# Sheet1.net
KiCad netlist of a schematic drawn in Altium Designer
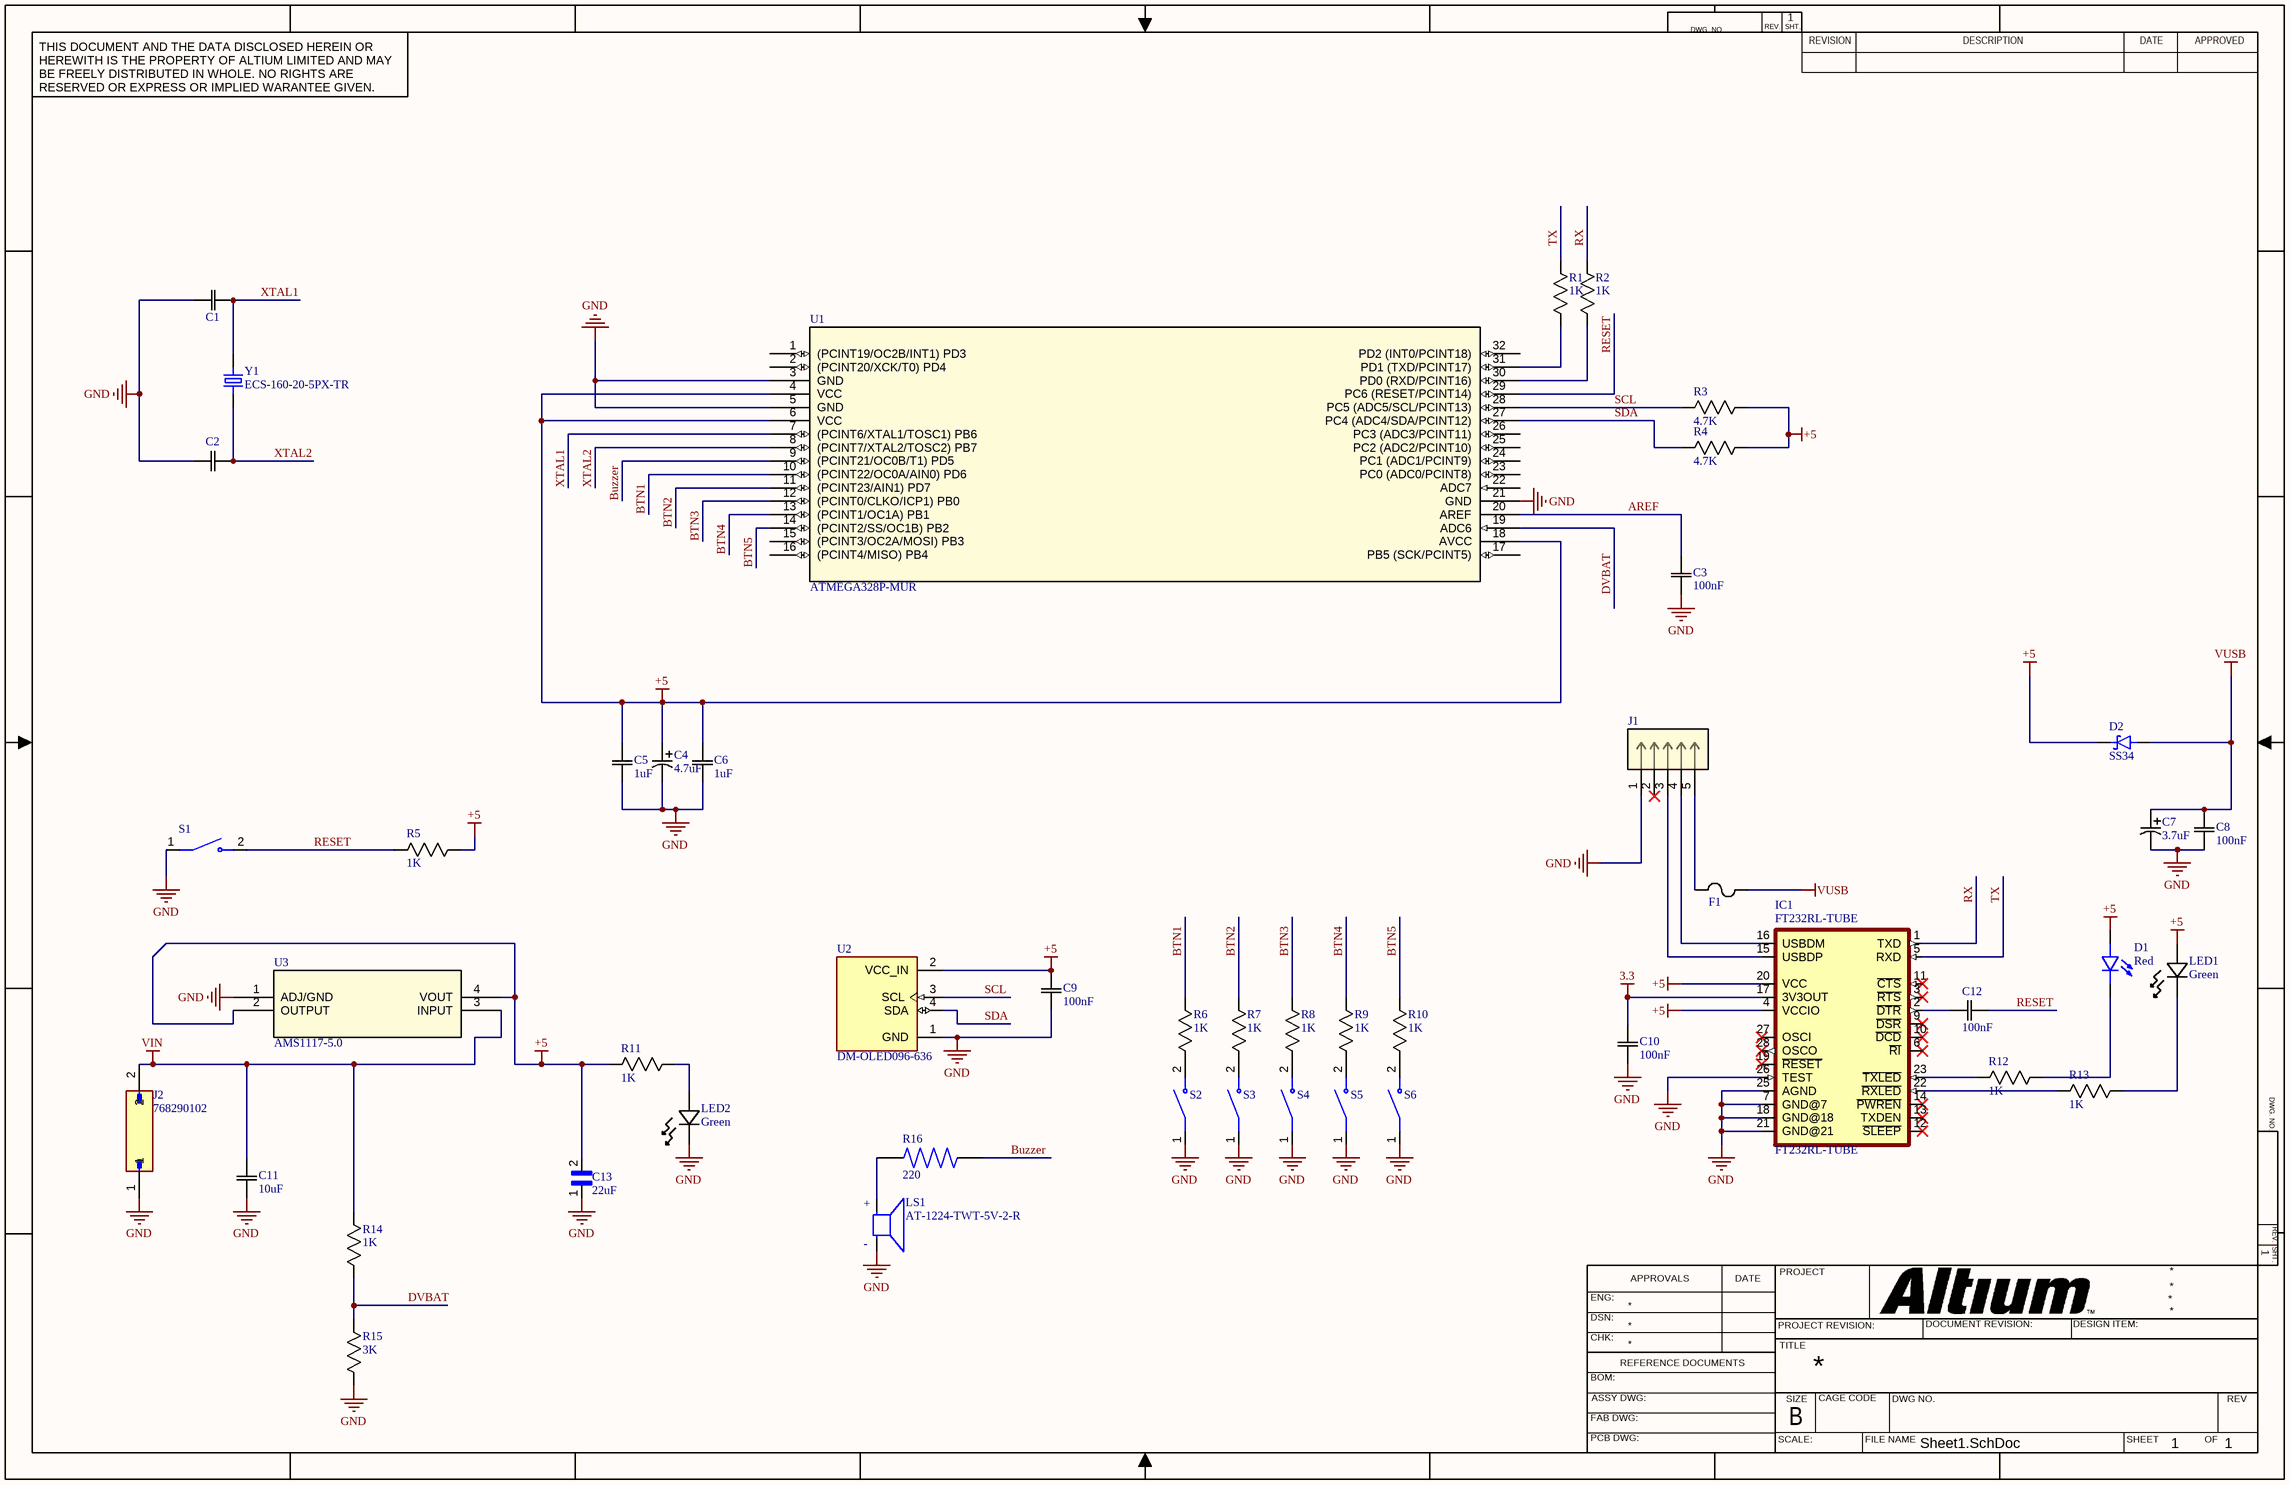
[diagram p0: Sheet1.SchDoc]

(export (version "E")
  (design (tool "Eeschema 10.0.6"))
  (components
    (comp (ref "C1")
      (value "CAP_18pfar_805pkg")
      (footprint "CAP_CC0805_YAG")
      (description "No Description Available")
      (libsource (lib "CAP_18pfar_805pkg") (part "CAP_18pfar_805pkg"))
    )
    (comp (ref "C2")
      (value "CAP_18pfar_805pkg")
      (footprint "CAP_CC0805_YAG")
      (description "No Description Available")
      (libsource (lib "CAP_18pfar_805pkg") (part "CAP_18pfar_805pkg"))
    )
    (comp (ref "C3")
      (value "100nF")
      (footprint "CC0805N_YAG")
      (description "No Description Available")
      (libsource (lib "CAP_100nF_805") (part "CC0805KRX7R9BB104"))
    )
    (comp (ref "C4")
      (value "4.7uF")
      (footprint "CAP_PAN_EEE_B_PAN")
      (description "No Description Available")
      (libsource (lib "CAP_4.7uF_El") (part "EEE-HA1E4R7R"))
    )
    (comp (ref "C5")
      (value "1uF")
      (footprint "CAP_CL21B105KAFNNNE_SAM")
      (description "No Description Available")
      (libsource (lib "CAP_1uF_805") (part "CL21B105KAFNNNE"))
    )
    (comp (ref "C6")
      (value "1uF")
      (footprint "CAP_CL21B105KAFNNNE_SAM")
      (description "No Description Available")
      (libsource (lib "CAP_1uF_805") (part "CL21B105KAFNNNE"))
    )
    (comp (ref "C7")
      (value "3.7uF")
      (footprint "CAP_PAN_EEE_B_PAN")
      (description "No Description Available")
      (libsource (lib "CAP_4.7uF_El") (part "EEE-HA1E4R7R"))
    )
    (comp (ref "C8")
      (value "100nF")
      (footprint "CC0805N_YAG")
      (description "No Description Available")
      (libsource (lib "CAP_100nF_805") (part "CC0805KRX7R9BB104"))
    )
    (comp (ref "C9")
      (value "100nF")
      (footprint "CC0805N_YAG")
      (description "No Description Available")
      (libsource (lib "CAP_100nF_805") (part "CC0805KRX7R9BB104"))
    )
    (comp (ref "C10")
      (value "100nF")
      (footprint "CC0805N_YAG")
      (description "No Description Available")
      (libsource (lib "CAP_100nF_805") (part "CC0805KRX7R9BB104"))
    )
    (comp (ref "C11")
      (value "10uF")
      (footprint "CAP_CL21_SAM")
      (description "No Description Available")
      (libsource (lib "CAP_10ufar_805pkg") (part "CAP_10ufar_805pkg"))
    )
    (comp (ref "C12")
      (value "100nF")
      (footprint "CC0805N_YAG")
      (description "No Description Available")
      (libsource (lib "CAP_100nF_805") (part "CC0805KRX7R9BB104"))
    )
    (comp (ref "C13")
      (value "22uF")
      (footprint "CAPC3225X280N")
      (description "SMD Capacitor X7R_EIA_ with Capacitance: 22uF Tol. 10%. Rated Voltage: 16Vdc")
      (fields (field (name "MP") "GCJ32ER71C226KE01L") (field (name "MF") "Murata"))
      (libsource (lib "CAP_22ufar_1210pkg") (part "GCJ32ER71C226KE01L"))
    )
    (comp (ref "D1")
      (value "Red")
      (footprint "LED_150060RS75000")
      (fields (field (name "MP") "150060RS75000"))
      (libsource (lib "RedLED") (part "150060RS75000"))
    )
    (comp (ref "D2")
      (value "SS34")
      (footprint "DIOM7959X265N")
      (description "Diode Schottky 40 V 3A Surface Mount SMC (DO-214AB)")
      (fields (field (name "MF") "onsemi"))
      (libsource (lib "SS34") (part "SS34"))
    )
    (comp (ref "F1")
      (value "MF-FSMF050X-2")
      (footprint "FUSE_MF-FSMF050X_BRN")
      (description "No Description Available")
      (libsource (lib "MF-FSMF050X-2") (part "MF-FSMF050X-2"))
    )
    (comp (ref "IC1")
      (value "FT232RL-TUBE")
      (footprint "SSOP28-LD")
      (description "USB Bridge, USB to UART USB 2.0 UART Interface 28-SSOP")
      (fields (field (name "MF") "FTDI,") (field (name "DIGI-KEY_PART_NUMBER") "768-1306-ND"))
      (libsource (lib "FT232RL-TUBE") (part "FT232RL-TUBE"))
    )
    (comp (ref "J1")
      (value "1734327-2")
      (footprint "CONN_1734327-2_TEC")
      (description "No Description Available")
      (libsource (lib "1734327-2") (part "1734327-2"))
    )
    (comp (ref "J2")
      (value "768290102")
      (footprint "MOLEX_768290102")
      (libsource (lib "768290102") (part "768290102"))
    )
    (comp (ref "LED1")
      (value "Green")
      (footprint "LED_150060GS75000_WRE")
      (description "No Description Available")
      (libsource (lib "GreenLED") (part "150060GS75000"))
    )
    (comp (ref "LED2")
      (value "Green")
      (footprint "LED_150060GS75000_WRE")
      (description "No Description Available")
      (libsource (lib "GreenLED") (part "150060GS75000"))
    )
    (comp (ref "LS1")
      (value "AT-1224-TWT-5V-2-R")
      (footprint "XDCR_AT-1224-TWT-5V-2-R")
      (description "AUDIO TRANSDUCER 12 VP-P 85 DB 2400 HZ")
      (libsource (lib "AT-1224-TWT-5V-2-R") (part "AT-1224-TWT-5V-2-R"))
    )
    (comp (ref "R1")
      (value "1K")
      (footprint "RC0805N_YAG")
      (description "No Description Available")
      (libsource (lib "RES_1K_805") (part "RC0805FR-071KL"))
    )
    (comp (ref "R2")
      (value "1K")
      (footprint "RC0805N_YAG")
      (description "No Description Available")
      (libsource (lib "RES_1K_805") (part "RC0805FR-071KL"))
    )
    (comp (ref "R3")
      (value "4.7K")
      (footprint "RES_CRCW_0805_VIS")
      (description "No Description Available")
      (libsource (lib "RES_4.7K_805") (part "CRCW08054K70FKEAC"))
    )
    (comp (ref "R4")
      (value "4.7K")
      (footprint "RES_CRCW_0805_VIS")
      (description "No Description Available")
      (libsource (lib "RES_4.7K_805") (part "CRCW08054K70FKEAC"))
    )
    (comp (ref "R5")
      (value "1K")
      (footprint "RC0805N_YAG")
      (description "No Description Available")
      (libsource (lib "RES_1K_805") (part "RC0805FR-071KL"))
    )
    (comp (ref "R6")
      (value "1K")
      (footprint "RC0805N_YAG")
      (description "No Description Available")
      (libsource (lib "RES_1K_805") (part "RC0805FR-071KL"))
    )
    (comp (ref "R7")
      (value "1K")
      (footprint "RC0805N_YAG")
      (description "No Description Available")
      (libsource (lib "RES_1K_805") (part "RC0805FR-071KL"))
    )
    (comp (ref "R8")
      (value "1K")
      (footprint "RC0805N_YAG")
      (description "No Description Available")
      (libsource (lib "RES_1K_805") (part "RC0805FR-071KL"))
    )
    (comp (ref "R9")
      (value "1K")
      (footprint "RC0805N_YAG")
      (description "No Description Available")
      (libsource (lib "RES_1K_805") (part "RC0805FR-071KL"))
    )
    (comp (ref "R10")
      (value "1K")
      (footprint "RC0805N_YAG")
      (description "No Description Available")
      (libsource (lib "RES_1K_805") (part "RC0805FR-071KL"))
    )
    (comp (ref "R11")
      (value "1K")
      (footprint "RC0805N_YAG")
      (description "No Description Available")
      (libsource (lib "RES_1K_805") (part "RC0805FR-071KL"))
    )
    (comp (ref "R12")
      (value "1K")
      (footprint "RC0805N_YAG")
      (description "No Description Available")
      (libsource (lib "RES_1K_805") (part "RC0805FR-071KL"))
    )
    (comp (ref "R13")
      (value "1K")
      (footprint "RC0805N_YAG")
      (description "No Description Available")
      (libsource (lib "RES_1K_805") (part "RC0805FR-071KL"))
    )
    (comp (ref "R14")
      (value "1K")
      (footprint "RC0805N_YAG")
      (description "No Description Available")
      (libsource (lib "RES_1K_805") (part "RC0805FR-071KL"))
    )
    (comp (ref "R15")
      (value "3K")
      (footprint "RES_CRG0805_TEC")
      (description "No Description Available")
      (libsource (lib "RES_3K_805") (part "CRG0805F3K0"))
    )
    (comp (ref "R16")
      (value "220")
      (footprint "RESC2012X65N")
      (description "Fixed Resistor CRGCQ 0805 220R 1%")
      (fields (field (name "MF") "TE Connectivity") (field (name "DIGI-KEY_PART_NUMBER") "A129741CT-ND"))
      (libsource (lib "RES_220_805") (part "CRGCQ0805F220R"))
    )
    (comp (ref "S1")
      (value "PTS636_SM43J_SMTR_LFS")
      (footprint "SW_PTS636_SM43J_SMTR_LFS")
      (description "Tactile Switch SPST-NO Top Actuated Surface Mount")
      (libsource (lib "PTS636_SM43J_SMTR_LFS") (part "PTS636_SM43J_SMTR_LFS"))
    )
    (comp (ref "S2")
      (value "PTS636_SM43J_SMTR_LFS")
      (footprint "SW_PTS636_SM43J_SMTR_LFS")
      (description "Tactile Switch SPST-NO Top Actuated Surface Mount")
      (libsource (lib "PTS636_SM43J_SMTR_LFS") (part "PTS636_SM43J_SMTR_LFS"))
    )
    (comp (ref "S3")
      (value "PTS636_SM43J_SMTR_LFS")
      (footprint "SW_PTS636_SM43J_SMTR_LFS")
      (description "Tactile Switch SPST-NO Top Actuated Surface Mount")
      (libsource (lib "PTS636_SM43J_SMTR_LFS") (part "PTS636_SM43J_SMTR_LFS"))
    )
    (comp (ref "S4")
      (value "PTS636_SM43J_SMTR_LFS")
      (footprint "SW_PTS636_SM43J_SMTR_LFS")
      (description "Tactile Switch SPST-NO Top Actuated Surface Mount")
      (libsource (lib "PTS636_SM43J_SMTR_LFS") (part "PTS636_SM43J_SMTR_LFS"))
    )
    (comp (ref "S5")
      (value "PTS636_SM43J_SMTR_LFS")
      (footprint "SW_PTS636_SM43J_SMTR_LFS")
      (description "Tactile Switch SPST-NO Top Actuated Surface Mount")
      (libsource (lib "PTS636_SM43J_SMTR_LFS") (part "PTS636_SM43J_SMTR_LFS"))
    )
    (comp (ref "S6")
      (value "PTS636_SM43J_SMTR_LFS")
      (footprint "SW_PTS636_SM43J_SMTR_LFS")
      (description "Tactile Switch SPST-NO Top Actuated Surface Mount")
      (libsource (lib "PTS636_SM43J_SMTR_LFS") (part "PTS636_SM43J_SMTR_LFS"))
    )
    (comp (ref "U1")
      (value "ATMEGA328P-MUR")
      (footprint "32M1-A_ATM")
      (description "No Description Available")
      (libsource (lib "ATMEGA328P-MUR") (part "ATMEGA328P-MUR"))
    )
    (comp (ref "U2")
      (value "DM-OLED096-636")
      (footprint "MODULE_DM-OLED096-636")
      (description "0.96â€ 128 X 64 MONOCHROME GRAPHIC OLED DISPLAY MODULE - I2C")
      (fields (field (name "MF") "Display Module"))
      (libsource (lib "DM-OLED096-636") (part "DM-OLED096-636"))
    )
    (comp (ref "U3")
      (value "AMS1117-5.0")
      (footprint "SOT_AMS1117-2.5_AMS")
      (description "No Description Available")
      (libsource (lib "AMS1117-5P0") (part "AMS1117-5.0"))
    )
    (comp (ref "Y1")
      (value "ECS-160-20-5PX-TR")
      (footprint "XTAL_ECS-160-20-5PX-TR")
      (description "16MHz Â±30ppm Crystal 20pF 40 Ohms HC-49/US")
      (fields (field (name "MF") "ECS Inc."))
      (libsource (lib "SnapEDAsch") (part "ECS-160-20-5PX-TR"))
    )
  )
  (nets
    (net (code "1") (name "+5") (class "Default")
      (node (ref "C13") (pin "2") (pinfunction "2_2") (pintype "passive"))
      (node (ref "C4") (pin "1") (pinfunction "1_1") (pintype "passive"))
      (node (ref "C5") (pin "2") (pinfunction "2_2") (pintype "passive"))
      (node (ref "C6") (pin "2") (pinfunction "2_2") (pintype "passive"))
      (node (ref "C9") (pin "2") (pinfunction "2_2") (pintype "passive"))
      (node (ref "D1") (pin "2") (pinfunction "A_2") (pintype "passive"))
      (node (ref "D2") (pin "C") (pinfunction "K_C") (pintype "passive"))
      (node (ref "IC1") (pin "20") (pinfunction "VCC_20") (pintype "power_in"))
      (node (ref "IC1") (pin "4") (pinfunction "VCCIO_4") (pintype "power_in"))
      (node (ref "LED1") (pin "2") (pinfunction "2_2") (pintype "passive"))
      (node (ref "R11") (pin "2") (pinfunction "2_2") (pintype "passive"))
      (node (ref "R3") (pin "2") (pinfunction "2_2") (pintype "passive"))
      (node (ref "R4") (pin "2") (pinfunction "2_2") (pintype "passive"))
      (node (ref "R5") (pin "1") (pinfunction "1_1") (pintype "passive"))
      (node (ref "U1") (pin "18") (pinfunction "AVCC_18") (pintype "power_in"))
      (node (ref "U1") (pin "4") (pinfunction "VCC_4") (pintype "power_in"))
      (node (ref "U1") (pin "6") (pinfunction "VCC_6") (pintype "power_in"))
      (node (ref "U2") (pin "2") (pinfunction "VCC_IN_2") (pintype "power_in"))
      (node (ref "U3") (pin "2") (pinfunction "OUTPUT_2") (pintype "passive"))
      (node (ref "U3") (pin "4") (pinfunction "VOUT_4") (pintype "passive"))
    )
    (net (code "2") (name "/AREF") (class "Default")
      (node (ref "C3") (pin "2") (pinfunction "2_2") (pintype "passive"))
      (node (ref "U1") (pin "20") (pinfunction "AREF_20") (pintype "passive"))
    )
    (net (code "3") (name "/BTN1") (class "Default")
      (node (ref "R6") (pin "1") (pinfunction "1_1") (pintype "passive"))
      (node (ref "U1") (pin "10") (pinfunction "(PCINT22/OC0A/AIN0)_PD6_10") (pintype "bidirectional"))
    )
    (net (code "4") (name "/BTN2") (class "Default")
      (node (ref "R7") (pin "1") (pinfunction "1_1") (pintype "passive"))
      (node (ref "U1") (pin "11") (pinfunction "(PCINT23/AIN1)_PD7_11") (pintype "bidirectional"))
    )
    (net (code "5") (name "/BTN3") (class "Default")
      (node (ref "R8") (pin "1") (pinfunction "1_1") (pintype "passive"))
      (node (ref "U1") (pin "12") (pinfunction "(PCINT0/CLKO/ICP1)_PB0_12") (pintype "bidirectional"))
    )
    (net (code "6") (name "/BTN4") (class "Default")
      (node (ref "R9") (pin "1") (pinfunction "1_1") (pintype "passive"))
      (node (ref "U1") (pin "13") (pinfunction "(PCINT1/OC1A)_PB1_13") (pintype "bidirectional"))
    )
    (net (code "7") (name "/BTN5") (class "Default")
      (node (ref "R10") (pin "1") (pinfunction "1_1") (pintype "passive"))
      (node (ref "U1") (pin "14") (pinfunction "(PCINT2/SS/OC1B)_PB2_14") (pintype "bidirectional"))
    )
    (net (code "8") (name "/Buzzer") (class "Default")
      (node (ref "R16") (pin "2") (pinfunction "2_2") (pintype "passive"))
      (node (ref "U1") (pin "9") (pinfunction "(PCINT21/OC0B/T1)_PD5_9") (pintype "bidirectional"))
    )
    (net (code "9") (name "/DVBAT") (class "Default")
      (node (ref "R14") (pin "2") (pinfunction "2_2") (pintype "passive"))
      (node (ref "R15") (pin "2") (pinfunction "2_2") (pintype "passive"))
      (node (ref "U1") (pin "19") (pinfunction "ADC6_19") (pintype "input"))
    )
    (net (code "10") (name "/RESET") (class "Default")
      (node (ref "C12") (pin "1") (pinfunction "1_1") (pintype "passive"))
      (node (ref "R5") (pin "2") (pinfunction "2_2") (pintype "passive"))
      (node (ref "S1") (pin "2") (pinfunction "NO_2") (pintype "passive"))
      (node (ref "U1") (pin "29") (pinfunction "PC6_(RESET/PCINT14)_29") (pintype "bidirectional"))
    )
    (net (code "11") (name "/RX") (class "Default")
      (node (ref "IC1") (pin "1") (pinfunction "TXD_1") (pintype "output"))
      (node (ref "R2") (pin "1") (pinfunction "1_1") (pintype "passive"))
    )
    (net (code "12") (name "/SCL") (class "Default")
      (node (ref "R3") (pin "1") (pinfunction "1_1") (pintype "passive"))
      (node (ref "U1") (pin "28") (pinfunction "PC5_(ADC5/SCL/PCINT13)_28") (pintype "bidirectional"))
      (node (ref "U2") (pin "3") (pinfunction "SCL_3") (pintype "input"))
    )
    (net (code "13") (name "/SDA") (class "Default")
      (node (ref "R4") (pin "1") (pinfunction "1_1") (pintype "passive"))
      (node (ref "U1") (pin "27") (pinfunction "PC4_(ADC4/SDA/PCINT12)_27") (pintype "bidirectional"))
      (node (ref "U2") (pin "4") (pinfunction "SDA_4") (pintype "bidirectional"))
    )
    (net (code "14") (name "/TX") (class "Default")
      (node (ref "IC1") (pin "5") (pinfunction "RXD_5") (pintype "input"))
      (node (ref "R1") (pin "1") (pinfunction "1_1") (pintype "passive"))
    )
    (net (code "15") (name "/XTAL1") (class "Default")
      (node (ref "C1") (pin "1") (pinfunction "1_1") (pintype "passive"))
      (node (ref "U1") (pin "7") (pinfunction "(PCINT6/XTAL1/TOSC1)_PB6_7") (pintype "bidirectional"))
      (node (ref "Y1") (pin "2") (pinfunction "2_2") (pintype "passive"))
    )
    (net (code "16") (name "/XTAL2") (class "Default")
      (node (ref "C2") (pin "2") (pinfunction "2_2") (pintype "passive"))
      (node (ref "U1") (pin "8") (pinfunction "(PCINT7/XTAL2/TOSC2)_PB7_8") (pintype "bidirectional"))
      (node (ref "Y1") (pin "1") (pinfunction "1_1") (pintype "passive"))
    )
    (net (code "17") (name "3.3") (class "Default")
      (node (ref "C10") (pin "2") (pinfunction "2_2") (pintype "passive"))
      (node (ref "IC1") (pin "17") (pinfunction "3V3OUT_17") (pintype "power_in"))
    )
    (net (code "18") (name "GND") (class "Default")
      (node (ref "C1") (pin "2") (pinfunction "2_2") (pintype "passive"))
      (node (ref "C10") (pin "1") (pinfunction "1_1") (pintype "passive"))
      (node (ref "C11") (pin "1") (pinfunction "1_1") (pintype "passive"))
      (node (ref "C13") (pin "1") (pinfunction "1_1") (pintype "passive"))
      (node (ref "C2") (pin "1") (pinfunction "1_1") (pintype "passive"))
      (node (ref "C3") (pin "1") (pinfunction "1_1") (pintype "passive"))
      (node (ref "C4") (pin "2") (pinfunction "2_2") (pintype "passive"))
      (node (ref "C5") (pin "1") (pinfunction "1_1") (pintype "passive"))
      (node (ref "C6") (pin "1") (pinfunction "1_1") (pintype "passive"))
      (node (ref "C7") (pin "2") (pinfunction "2_2") (pintype "passive"))
      (node (ref "C8") (pin "1") (pinfunction "1_1") (pintype "passive"))
      (node (ref "C9") (pin "1") (pinfunction "1_1") (pintype "passive"))
      (node (ref "IC1") (pin "18") (pinfunction "GND@18_18") (pintype "power_in"))
      (node (ref "IC1") (pin "21") (pinfunction "GND@21_21") (pintype "power_in"))
      (node (ref "IC1") (pin "25") (pinfunction "AGND_25") (pintype "power_in"))
      (node (ref "IC1") (pin "26") (pinfunction "TEST_26") (pintype "input"))
      (node (ref "IC1") (pin "7") (pinfunction "GND@7_7") (pintype "power_in"))
      (node (ref "J1") (pin "1") (pinfunction "1_1") (pintype "passive"))
      (node (ref "J2") (pin "1") (pinfunction "1_1") (pintype "passive"))
      (node (ref "LED2") (pin "1") (pinfunction "1_1") (pintype "passive"))
      (node (ref "LS1") (pin "N") (pinfunction "N_N") (pintype "passive"))
      (node (ref "R15") (pin "1") (pinfunction "1_1") (pintype "passive"))
      (node (ref "S1") (pin "1") (pinfunction "COM_1") (pintype "passive"))
      (node (ref "S2") (pin "1") (pinfunction "COM_1") (pintype "passive"))
      (node (ref "S3") (pin "1") (pinfunction "COM_1") (pintype "passive"))
      (node (ref "S4") (pin "1") (pinfunction "COM_1") (pintype "passive"))
      (node (ref "S5") (pin "1") (pinfunction "COM_1") (pintype "passive"))
      (node (ref "S6") (pin "1") (pinfunction "COM_1") (pintype "passive"))
      (node (ref "U1") (pin "21") (pinfunction "GND_21") (pintype "power_in"))
      (node (ref "U1") (pin "3") (pinfunction "GND_3") (pintype "power_in"))
      (node (ref "U1") (pin "5") (pinfunction "GND_5") (pintype "power_in"))
      (node (ref "U2") (pin "1") (pinfunction "GND_1") (pintype "power_in"))
      (node (ref "U3") (pin "1") (pinfunction "ADJ/GND_1") (pintype "passive"))
    )
    (net (code "19") (name "Net-(D1-C)") (class "Default")
      (node (ref "D1") (pin "1") (pinfunction "C_1") (pintype "passive"))
      (node (ref "R12") (pin "1") (pinfunction "1_1") (pintype "passive"))
    )
    (net (code "20") (name "Net-(F1-Pad1)") (class "Default")
      (node (ref "F1") (pin "1") (pinfunction "1_1") (pintype "passive"))
      (node (ref "J1") (pin "5") (pinfunction "5_5") (pintype "passive"))
    )
    (net (code "21") (name "Net-(IC1-USBDM)") (class "Default")
      (node (ref "IC1") (pin "16") (pinfunction "USBDM_16") (pintype "bidirectional"))
      (node (ref "J1") (pin "4") (pinfunction "4_4") (pintype "passive"))
    )
    (net (code "22") (name "Net-(IC1-USBDP)") (class "Default")
      (node (ref "IC1") (pin "15") (pinfunction "USBDP_15") (pintype "bidirectional"))
      (node (ref "J1") (pin "3") (pinfunction "3_3") (pintype "passive"))
    )
    (net (code "23") (name "Net-(IC1-~{DTR})") (class "Default")
      (node (ref "C12") (pin "2") (pinfunction "2_2") (pintype "passive"))
      (node (ref "IC1") (pin "2") (pinfunction "~{DTR}_2") (pintype "output"))
    )
    (net (code "24") (name "Net-(IC1-~{RXLED})") (class "Default")
      (node (ref "IC1") (pin "22") (pinfunction "~{RXLED}_22") (pintype "input"))
      (node (ref "R13") (pin "2") (pinfunction "2_2") (pintype "passive"))
    )
    (net (code "25") (name "Net-(IC1-~{TXLED})") (class "Default")
      (node (ref "IC1") (pin "23") (pinfunction "~{TXLED}_23") (pintype "input"))
      (node (ref "R12") (pin "2") (pinfunction "2_2") (pintype "passive"))
    )
    (net (code "26") (name "Net-(LED1-Pad1)") (class "Default")
      (node (ref "LED1") (pin "1") (pinfunction "1_1") (pintype "passive"))
      (node (ref "R13") (pin "1") (pinfunction "1_1") (pintype "passive"))
    )
    (net (code "27") (name "Net-(LED2-Pad2)") (class "Default")
      (node (ref "LED2") (pin "2") (pinfunction "2_2") (pintype "passive"))
      (node (ref "R11") (pin "1") (pinfunction "1_1") (pintype "passive"))
    )
    (net (code "28") (name "Net-(LS1-PadP)") (class "Default")
      (node (ref "LS1") (pin "P") (pinfunction "P_P") (pintype "passive"))
      (node (ref "R16") (pin "1") (pinfunction "1_1") (pintype "passive"))
    )
    (net (code "29") (name "Net-(S2-NO)") (class "Default")
      (node (ref "R6") (pin "2") (pinfunction "2_2") (pintype "passive"))
      (node (ref "S2") (pin "2") (pinfunction "NO_2") (pintype "passive"))
    )
    (net (code "30") (name "Net-(S3-NO)") (class "Default")
      (node (ref "R7") (pin "2") (pinfunction "2_2") (pintype "passive"))
      (node (ref "S3") (pin "2") (pinfunction "NO_2") (pintype "passive"))
    )
    (net (code "31") (name "Net-(S4-NO)") (class "Default")
      (node (ref "R8") (pin "2") (pinfunction "2_2") (pintype "passive"))
      (node (ref "S4") (pin "2") (pinfunction "NO_2") (pintype "passive"))
    )
    (net (code "32") (name "Net-(S5-NO)") (class "Default")
      (node (ref "R9") (pin "2") (pinfunction "2_2") (pintype "passive"))
      (node (ref "S5") (pin "2") (pinfunction "NO_2") (pintype "passive"))
    )
    (net (code "33") (name "Net-(S6-NO)") (class "Default")
      (node (ref "R10") (pin "2") (pinfunction "2_2") (pintype "passive"))
      (node (ref "S6") (pin "2") (pinfunction "NO_2") (pintype "passive"))
    )
    (net (code "34") (name "Net-(U1-PD0_(RXD{slash}PCINT16))") (class "Default")
      (node (ref "R2") (pin "2") (pinfunction "2_2") (pintype "passive"))
      (node (ref "U1") (pin "30") (pinfunction "PD0_(RXD/PCINT16)_30") (pintype "bidirectional"))
    )
    (net (code "35") (name "Net-(U1-PD1_(TXD{slash}PCINT17))") (class "Default")
      (node (ref "R1") (pin "2") (pinfunction "2_2") (pintype "passive"))
      (node (ref "U1") (pin "31") (pinfunction "PD1_(TXD/PCINT17)_31") (pintype "bidirectional"))
    )
    (net (code "36") (name "VIN") (class "Default")
      (node (ref "C11") (pin "2") (pinfunction "2_2") (pintype "passive"))
      (node (ref "J2") (pin "2") (pinfunction "2_2") (pintype "passive"))
      (node (ref "R14") (pin "1") (pinfunction "1_1") (pintype "passive"))
      (node (ref "U3") (pin "3") (pinfunction "INPUT_3") (pintype "passive"))
    )
    (net (code "37") (name "VUSB") (class "Default")
      (node (ref "C7") (pin "1") (pinfunction "1_1") (pintype "passive"))
      (node (ref "C8") (pin "2") (pinfunction "2_2") (pintype "passive"))
      (node (ref "D2") (pin "A") (pinfunction "A_A") (pintype "passive"))
      (node (ref "F1") (pin "2") (pinfunction "2_2") (pintype "passive"))
    )
    (net (code "38") (name "unconnected-(IC1-OSCI-Pad27)") (class "Default")
      (node (ref "IC1") (pin "27") (pinfunction "OSCI_27") (pintype "passive+no_connect"))
    )
    (net (code "39") (name "unconnected-(IC1-OSCO-Pad28)") (class "Default")
      (node (ref "IC1") (pin "28") (pinfunction "OSCO_28") (pintype "output+no_connect"))
    )
    (net (code "40") (name "unconnected-(IC1-TXDEN-Pad13)") (class "Default")
      (node (ref "IC1") (pin "13") (pinfunction "TXDEN_13") (pintype "passive+no_connect"))
    )
    (net (code "41") (name "unconnected-(IC1-~{CTS}-Pad11)") (class "Default")
      (node (ref "IC1") (pin "11") (pinfunction "~{CTS}_11") (pintype "input+no_connect"))
    )
    (net (code "42") (name "unconnected-(IC1-~{DCD}-Pad10)") (class "Default")
      (node (ref "IC1") (pin "10") (pinfunction "~{DCD}_10") (pintype "passive+no_connect"))
    )
    (net (code "43") (name "unconnected-(IC1-~{DSR}-Pad9)") (class "Default")
      (node (ref "IC1") (pin "9") (pinfunction "~{DSR}_9") (pintype "passive+no_connect"))
    )
    (net (code "44") (name "unconnected-(IC1-~{PWREN}-Pad14)") (class "Default")
      (node (ref "IC1") (pin "14") (pinfunction "~{PWREN}_14") (pintype "passive+no_connect"))
    )
    (net (code "45") (name "unconnected-(IC1-~{RESET}-Pad19)") (class "Default")
      (node (ref "IC1") (pin "19") (pinfunction "~{RESET}_19") (pintype "passive+no_connect"))
    )
    (net (code "46") (name "unconnected-(IC1-~{RI}-Pad6)") (class "Default")
      (node (ref "IC1") (pin "6") (pinfunction "~{RI}_6") (pintype "passive+no_connect"))
    )
    (net (code "47") (name "unconnected-(IC1-~{RTS}-Pad3)") (class "Default")
      (node (ref "IC1") (pin "3") (pinfunction "~{RTS}_3") (pintype "output+no_connect"))
    )
    (net (code "48") (name "unconnected-(IC1-~{SLEEP}-Pad12)") (class "Default")
      (node (ref "IC1") (pin "12") (pinfunction "~{SLEEP}_12") (pintype "passive+no_connect"))
    )
    (net (code "49") (name "unconnected-(J1-Pad2)") (class "Default")
      (node (ref "J1") (pin "2") (pinfunction "2_2") (pintype "passive+no_connect"))
    )
    (net (code "50") (name "unconnected-(U1-(PCINT3{slash}OC2A{slash}MOSI)_PB3-Pad15)") (class "Default")
      (node (ref "U1") (pin "15") (pinfunction "(PCINT3/OC2A/MOSI)_PB3_15") (pintype "bidirectional"))
    )
    (net (code "51") (name "unconnected-(U1-(PCINT4{slash}MISO)_PB4-Pad16)") (class "Default")
      (node (ref "U1") (pin "16") (pinfunction "(PCINT4/MISO)_PB4_16") (pintype "bidirectional"))
    )
    (net (code "52") (name "unconnected-(U1-(PCINT19{slash}OC2B{slash}INT1)_PD3-Pad1)") (class "Default")
      (node (ref "U1") (pin "1") (pinfunction "(PCINT19/OC2B/INT1)_PD3_1") (pintype "bidirectional"))
    )
    (net (code "53") (name "unconnected-(U1-(PCINT20{slash}XCK{slash}T0)_PD4-Pad2)") (class "Default")
      (node (ref "U1") (pin "2") (pinfunction "(PCINT20/XCK/T0)_PD4_2") (pintype "bidirectional"))
    )
    (net (code "54") (name "unconnected-(U1-ADC7-Pad22)") (class "Default")
      (node (ref "U1") (pin "22") (pinfunction "ADC7_22") (pintype "input"))
    )
    (net (code "55") (name "unconnected-(U1-PB5_(SCK{slash}PCINT5)-Pad17)") (class "Default")
      (node (ref "U1") (pin "17") (pinfunction "PB5_(SCK/PCINT5)_17") (pintype "bidirectional"))
    )
    (net (code "56") (name "unconnected-(U1-PC0_(ADC0{slash}PCINT8)-Pad23)") (class "Default")
      (node (ref "U1") (pin "23") (pinfunction "PC0_(ADC0/PCINT8)_23") (pintype "bidirectional"))
    )
    (net (code "57") (name "unconnected-(U1-PC1_(ADC1{slash}PCINT9)-Pad24)") (class "Default")
      (node (ref "U1") (pin "24") (pinfunction "PC1_(ADC1/PCINT9)_24") (pintype "bidirectional"))
    )
    (net (code "58") (name "unconnected-(U1-PC2_(ADC2{slash}PCINT10)-Pad25)") (class "Default")
      (node (ref "U1") (pin "25") (pinfunction "PC2_(ADC2/PCINT10)_25") (pintype "bidirectional"))
    )
    (net (code "59") (name "unconnected-(U1-PC3_(ADC3{slash}PCINT11)-Pad26)") (class "Default")
      (node (ref "U1") (pin "26") (pinfunction "PC3_(ADC3/PCINT11)_26") (pintype "bidirectional"))
    )
    (net (code "60") (name "unconnected-(U1-PD2_(INT0{slash}PCINT18)-Pad32)") (class "Default")
      (node (ref "U1") (pin "32") (pinfunction "PD2_(INT0/PCINT18)_32") (pintype "bidirectional"))
    )
  )
)
